# PX4FLOW2_0_Connectors_X0.net
KiCad netlist of a schematic drawn in Altium Designer
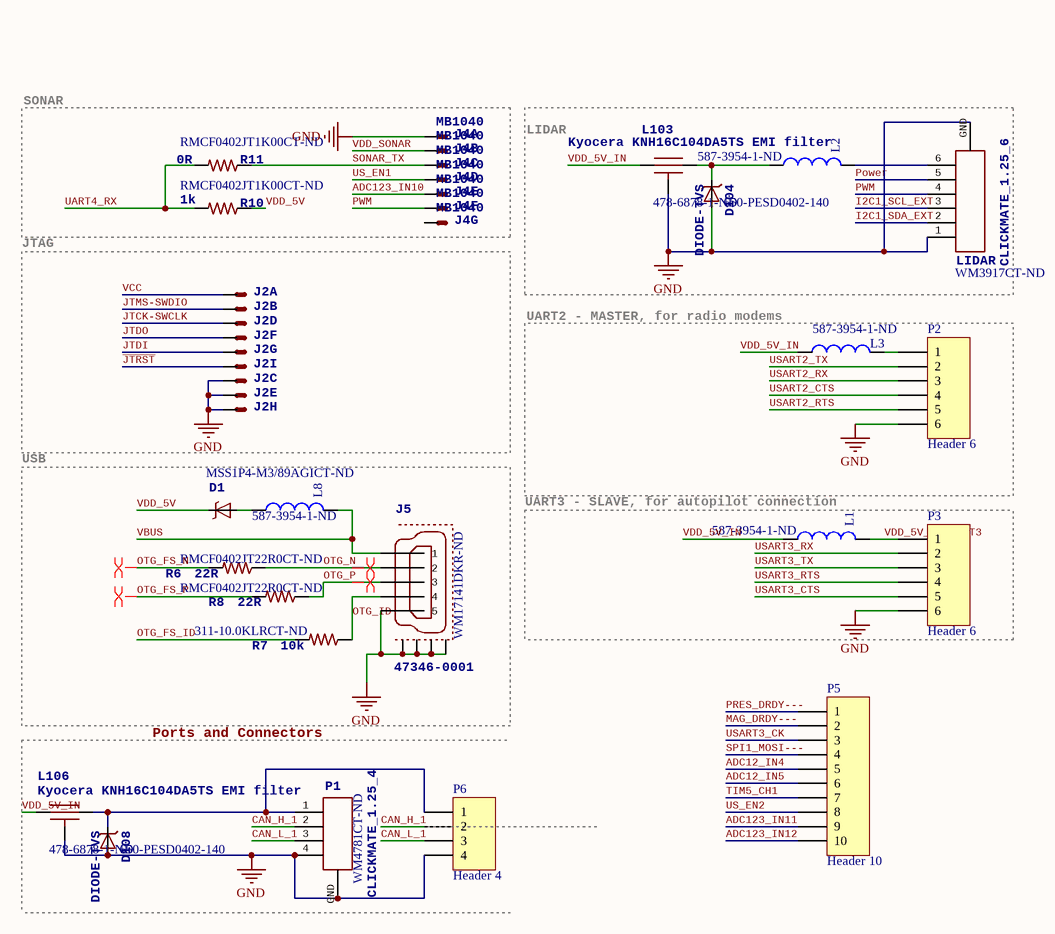
[diagram p0: PX4FLOW2.0_Connectors_X0.SchDoc]

(export (version "E")
  (design (tool "Eeschema 10.0.6"))
  (components
    (comp (ref "D1")
      (value "MSS1P4-M3")
      (footprint "MICROSMP")
      (description "Schottky barrier diode in DO214AC, e.g. Fairchild SS14.")
      (fields (field (name "SUPPLIER PART NUMBER 1") "MSS1P4-M3/89AGICT-ND"))
      (libsource (lib "pixhawk2") (part "DIODE-SCHOTTKY_MSMP"))
    )
    (comp (ref "D104")
      (value "DIODE-TVS")
      (footprint "0402-TVS")
      (description "Diode, TVS, 14VWM, 40VC, 0402, SMD")
      (fields
        (field (name "SUPPLIER PART NUMBER 1") "650-PESD0402-140")
        (field (name "3DR_PARTNO") "ECM0837")
      )
      (libsource (lib "PCA_0005_FULL_CB_REV_A") (part "DIODE-TVS"))
    )
    (comp (ref "D108")
      (value "DIODE-TVS")
      (footprint "0402-TVS")
      (description "Diode, TVS, 14VWM, 40VC, 0402, SMD")
      (fields
        (field (name "SUPPLIER PART NUMBER 1") "650-PESD0402-140")
        (field (name "3DR_PARTNO") "ECM0837")
      )
      (libsource (lib "PCA_0005_FULL_CB_REV_A") (part "DIODE-TVS"))
    )
    (comp (ref "J2")
      (value "~")
      (footprint "FTSH-105-01-XXX-DV-K")
      (libsource (lib "pixhawk2") (part "ARM_MINI_JTAG-SMT"))
    )
    (comp (ref "J4") (value "MB1040") (footprint "MAXSONAR") (libsource (lib "pixhawk2") (part "MAXSONAR")))
    (comp (ref "J5")
      (value "47346-0001")
      (footprint "MOLEX-47346-0001")
      (description "MICRO USB B, BOTTOM MOUNT")
      (fields
        (field (name "SUPPLIER PART NUMBER 1") "WM17141DKR-ND")
        (field (name "3DR_PARTNO") "ECM0486")
        (field (name "PARTNO") "0473460001")
      )
      (libsource (lib "pixhawk2") (part "MOLEX-47346-0001"))
    )
    (comp (ref "L1")
      (value "Inductor")
      (footprint "L0402")
      (description "FERRITE BEAD 120 OHM 0402")
      (fields (field (name "SUPPLIER PART NUMBER 1") "587-3954-1-ND"))
      (libsource (lib "3DR") (part "Inductor"))
    )
    (comp (ref "L2")
      (value "Inductor")
      (footprint "L0402")
      (description "FERRITE BEAD 120 OHM 0402")
      (fields (field (name "SUPPLIER PART NUMBER 1") "587-3954-1-ND"))
      (libsource (lib "3DR") (part "Inductor"))
    )
    (comp (ref "L3")
      (value "Inductor")
      (footprint "L0402")
      (description "FERRITE BEAD 120 OHM 0402")
      (fields (field (name "SUPPLIER PART NUMBER 1") "587-3954-1-ND"))
      (libsource (lib "3DR") (part "Inductor"))
    )
    (comp (ref "L8")
      (value "FERRITE BEAD 120 OHM 0402")
      (footprint "L0402")
      (fields (field (name "SUPPLIER PART NUMBER 1") "587-3954-1-ND"))
      (libsource (lib "3DR") (part "Inductor"))
    )
    (comp (ref "L103")
      (value "Kyocera KNH16C104DA5TS EMI filter")
      (footprint "KYOCERA-KNH16-DA")
      (description "Capacitor, Filter, 0.1uF, 25V, 2A, 0603, SMD")
      (fields (field (name "SUPPLIER PART NUMBER 1") "478-6878-1-ND") (field (name "3DR_PARTNO") "ECM0719"))
      (libsource (lib "PCA_0005_FULL_CB_REV_A") (part "KNH16C104DA5TS"))
    )
    (comp (ref "L106")
      (value "Kyocera KNH16C104DA5TS EMI filter")
      (footprint "KYOCERA-KNH16-DA")
      (description "Capacitor, Filter, 0.1uF, 25V, 2A, 0603, SMD")
      (fields (field (name "SUPPLIER PART NUMBER 1") "478-6878-1-ND") (field (name "3DR_PARTNO") "ECM0719"))
      (libsource (lib "PCA_0005_FULL_CB_REV_A") (part "KNH16C104DA5TS"))
    )
    (comp (ref "LIDAR")
      (value "CLICKMATE_1.25_6")
      (footprint "CLICKMATE_H6")
      (description "1.25 W/B SGL R/A REC ASSY 6CKT")
      (fields (field (name "3DR_PARTNO") "ECM0532") (field (name "SUPPLIER PART NUMBER 1") "WM3917CT-ND"))
      (libsource (lib "PCA_0005_FULL_CB_REV_A") (part "CLICKMATE_1.25_6"))
    )
    (comp (ref "P1")
      (value "CLICKMATE_1.25_4")
      (footprint "CLICKMATE_V4")
      (description "Connector, Rcpt, 4Pos, 1.25MM, W/B, VERT, SMD, Tin")
      (fields (field (name "SUPPLIER PART NUMBER 1") "WM4781CT-ND") (field (name "3DR_PARTNO") "PRT0441"))
      (libsource (lib "PCA_0005_FULL_CB_REV_A") (part "CLICKMATE_1.25_4"))
    )
    (comp (ref "P2")
      (value "Header 6")
      (footprint "HDR1X6")
      (description "Header, 6-Pin")
      (fields (field (name "PUBLISHER") "Altium Limited"))
      (libsource (lib "Miscellaneous Connectors") (part "Header 6"))
    )
    (comp (ref "P3")
      (value "Header 6")
      (footprint "HDR1X6")
      (description "Header, 6-Pin")
      (fields (field (name "PUBLISHER") "Altium Limited"))
      (libsource (lib "Miscellaneous Connectors") (part "Header 6"))
    )
    (comp (ref "P5")
      (value "Header 10")
      (footprint "HDR1X10")
      (description "Header, 10-Pin")
      (fields (field (name "PUBLISHER") "Altium Limited"))
      (libsource (lib "Miscellaneous Connectors") (part "Header 10"))
    )
    (comp (ref "P6")
      (value "Header 4")
      (footprint "HDR1X4")
      (description "Header, 4-Pin")
      (fields (field (name "PUBLISHER") "Altium Limited"))
      (libsource (lib "Miscellaneous Connectors") (part "Header 4"))
    )
    (comp (ref "R6")
      (value "22R")
      (footprint "R0402")
      (fields
        (field (name "PARTNO") "RMCF0402JT22R0")
        (field (name "SUPPLIER PART NUMBER 1") "RMCF0402JT22R0CT-ND")
      )
      (libsource (lib "pixhawk2") (part "RESISTOR0402-RES"))
    )
    (comp (ref "R7")
      (value "10k")
      (footprint "R0402")
      (description "RES 10K OHM 1/16W 1% 0402 SMD")
      (fields
        (field (name "PARTNO") "MFR-25FBF-10K0")
        (field (name "SUPPLIER PART NUMBER 1") "311-10.0KLRCT-ND")
      )
      (libsource (lib "pixhawk2") (part "RESISTOR0402-RES"))
    )
    (comp (ref "R8")
      (value "22R")
      (footprint "R0402")
      (fields
        (field (name "PARTNO") "RMCF0402JT22R0")
        (field (name "SUPPLIER PART NUMBER 1") "RMCF0402JT22R0CT-ND")
      )
      (libsource (lib "pixhawk2") (part "RESISTOR0402-RES"))
    )
    (comp (ref "R10")
      (value "1k")
      (footprint "R0402")
      (fields
        (field (name "PARTNO") "RMCF0402JT1K00")
        (field (name "SUPPLIER PART NUMBER 1") "RMCF0402JT1K00CT-ND")
      )
      (libsource (lib "pixhawk2") (part "RESISTOR0402-RES"))
    )
    (comp (ref "R11")
      (value "0R")
      (footprint "R0402")
      (fields
        (field (name "PARTNO") "RMCF0402JT1K00")
        (field (name "SUPPLIER PART NUMBER 1") "RMCF0402JT1K00CT-ND")
      )
      (libsource (lib "pixhawk2") (part "RESISTOR0402-RES"))
    )
  )
  (nets
    (net (code "1") (name "/ADC12_IN4") (class "Default")
      (node (ref "P5") (pin "5") (pinfunction "5_5") (pintype "passive"))
    )
    (net (code "2") (name "/ADC12_IN5") (class "Default")
      (node (ref "P5") (pin "6") (pinfunction "6_6") (pintype "passive"))
    )
    (net (code "3") (name "/ADC123_IN10") (class "Default")
      (node (ref "J4") (pin "AN") (pinfunction "S_AN") (pintype "passive"))
    )
    (net (code "4") (name "/ADC123_IN11") (class "Default")
      (node (ref "P5") (pin "9") (pinfunction "9_9") (pintype "passive"))
    )
    (net (code "5") (name "/ADC123_IN12") (class "Default")
      (node (ref "P5") (pin "10") (pinfunction "10_10") (pintype "passive"))
    )
    (net (code "6") (name "/CAN_H_1") (class "Default")
      (node (ref "P1") (pin "2") (pinfunction "2_2") (pintype "passive"))
      (node (ref "P6") (pin "2") (pinfunction "2_2") (pintype "passive"))
    )
    (net (code "7") (name "/CAN_L_1") (class "Default")
      (node (ref "P1") (pin "3") (pinfunction "3_3") (pintype "passive"))
      (node (ref "P6") (pin "3") (pinfunction "3_3") (pintype "passive"))
    )
    (net (code "8") (name "/I2C1_SCL_EXT") (class "Default")
      (node (ref "LIDAR") (pin "3") (pinfunction "3_3") (pintype "passive"))
    )
    (net (code "9") (name "/I2C1_SDA_EXT") (class "Default")
      (node (ref "LIDAR") (pin "2") (pinfunction "2_2") (pintype "passive"))
    )
    (net (code "10") (name "/JTCK-SWCLK") (class "Default")
      (node (ref "J2") (pin "4") (pinfunction "S_4") (pintype "passive"))
    )
    (net (code "11") (name "/JTDI") (class "Default")
      (node (ref "J2") (pin "8") (pinfunction "S_8") (pintype "passive"))
    )
    (net (code "12") (name "/JTDO") (class "Default")
      (node (ref "J2") (pin "6") (pinfunction "S_6") (pintype "passive"))
    )
    (net (code "13") (name "/JTMS-SWDIO") (class "Default")
      (node (ref "J2") (pin "2") (pinfunction "S_2") (pintype "passive"))
    )
    (net (code "14") (name "/MAG_DRDY---") (class "Default")
      (node (ref "P5") (pin "2") (pinfunction "2_2") (pintype "passive"))
    )
    (net (code "15") (name "/OTG_FS_ID") (class "Default")
      (node (ref "R7") (pin "2") (pinfunction "2_2") (pintype "passive"))
    )
    (net (code "16") (name "/OTG_FS_N") (class "Default")
      (node (ref "R6") (pin "2") (pinfunction "2_2") (pintype "passive"))
    )
    (net (code "17") (name "/OTG_FS_P") (class "Default")
      (node (ref "R8") (pin "2") (pinfunction "2_2") (pintype "passive"))
    )
    (net (code "18") (name "/OTG_ID") (class "Default")
      (node (ref "J5") (pin "ID") (pinfunction "4_ID") (pintype "passive"))
      (node (ref "R7") (pin "1") (pinfunction "1_1") (pintype "passive"))
    )
    (net (code "19") (name "/OTG_N") (class "Default")
      (node (ref "J5") (pin "D-") (pinfunction "2_D-") (pintype "passive"))
      (node (ref "R6") (pin "1") (pinfunction "1_1") (pintype "passive"))
    )
    (net (code "20") (name "/OTG_P") (class "Default")
      (node (ref "J5") (pin "D+") (pinfunction "3_D+") (pintype "passive"))
      (node (ref "R8") (pin "1") (pinfunction "1_1") (pintype "passive"))
    )
    (net (code "21") (name "/PRES_DRDY---") (class "Default")
      (node (ref "P5") (pin "1") (pinfunction "1_1") (pintype "passive"))
    )
    (net (code "22") (name "/PWM") (class "Default")
      (node (ref "J4") (pin "PW") (pinfunction "S_PW") (pintype "passive"))
      (node (ref "LIDAR") (pin "4") (pinfunction "4_4") (pintype "passive"))
    )
    (net (code "23") (name "/Power") (class "Default")
      (node (ref "LIDAR") (pin "5") (pinfunction "5_5") (pintype "passive"))
    )
    (net (code "24") (name "/SONAR_TX") (class "Default")
      (node (ref "J4") (pin "TX") (pinfunction "S_TX") (pintype "passive"))
      (node (ref "R11") (pin "1") (pinfunction "1_1") (pintype "passive"))
    )
    (net (code "25") (name "/SPI1_MOSI---") (class "Default")
      (node (ref "P5") (pin "4") (pinfunction "4_4") (pintype "passive"))
    )
    (net (code "26") (name "/TIM5_CH1") (class "Default")
      (node (ref "P5") (pin "7") (pinfunction "7_7") (pintype "passive"))
    )
    (net (code "27") (name "/UART4_RX") (class "Default")
      (node (ref "R10") (pin "2") (pinfunction "2_2") (pintype "passive"))
      (node (ref "R11") (pin "2") (pinfunction "2_2") (pintype "passive"))
    )
    (net (code "28") (name "/USART2_CTS") (class "Default")
      (node (ref "P2") (pin "4") (pinfunction "4_4") (pintype "passive"))
    )
    (net (code "29") (name "/USART2_RTS") (class "Default")
      (node (ref "P2") (pin "5") (pinfunction "5_5") (pintype "passive"))
    )
    (net (code "30") (name "/USART2_RX") (class "Default")
      (node (ref "P2") (pin "3") (pinfunction "3_3") (pintype "passive"))
    )
    (net (code "31") (name "/USART2_TX") (class "Default")
      (node (ref "P2") (pin "2") (pinfunction "2_2") (pintype "passive"))
    )
    (net (code "32") (name "/USART3_CK") (class "Default")
      (node (ref "P5") (pin "3") (pinfunction "3_3") (pintype "passive"))
    )
    (net (code "33") (name "/USART3_CTS") (class "Default")
      (node (ref "P3") (pin "5") (pinfunction "5_5") (pintype "passive"))
    )
    (net (code "34") (name "/USART3_RTS") (class "Default")
      (node (ref "P3") (pin "4") (pinfunction "4_4") (pintype "passive"))
    )
    (net (code "35") (name "/USART3_RX") (class "Default")
      (node (ref "P3") (pin "2") (pinfunction "2_2") (pintype "passive"))
    )
    (net (code "36") (name "/USART3_TX") (class "Default")
      (node (ref "P3") (pin "3") (pinfunction "3_3") (pintype "passive"))
    )
    (net (code "37") (name "/US_EN1") (class "Default")
      (node (ref "J4") (pin "RX") (pinfunction "S_RX") (pintype "passive"))
    )
    (net (code "38") (name "/US_EN2") (class "Default")
      (node (ref "P5") (pin "8") (pinfunction "8_8") (pintype "passive"))
    )
    (net (code "39") (name "/VBUS") (class "Default")
      (node (ref "J5") (pin "VBUS") (pinfunction "1_VBUS") (pintype "open_emitter"))
      (node (ref "L8") (pin "2") (pinfunction "2_2") (pintype "passive"))
    )
    (net (code "40") (name "/VCC") (class "Default")
      (node (ref "J2") (pin "1") (pinfunction "S_1") (pintype "passive"))
    )
    (net (code "41") (name "/VDD_5V") (class "Default")
      (node (ref "D1") (pin "CATHODE") (pinfunction "C_CATHODE") (pintype "passive"))
      (node (ref "R10") (pin "1") (pinfunction "1_1") (pintype "passive"))
    )
    (net (code "42") (name "/VDD_5V_IN") (class "Default")
      (node (ref "L1") (pin "1") (pinfunction "1_1") (pintype "passive"))
      (node (ref "L103") (pin "P$1") (pinfunction "P$1_P$1") (pintype "passive"))
      (node (ref "L106") (pin "P$1") (pinfunction "P$1_P$1") (pintype "passive"))
      (node (ref "L3") (pin "1") (pinfunction "1_1") (pintype "passive"))
    )
    (net (code "43") (name "/VDD_5V_IN_UART3") (class "Default")
      (node (ref "L1") (pin "2") (pinfunction "2_2") (pintype "passive"))
      (node (ref "P3") (pin "1") (pinfunction "1_1") (pintype "passive"))
    )
    (net (code "44") (name "/VDD_SONAR") (class "Default")
      (node (ref "J4") (pin "VDD") (pinfunction "S_VDD") (pintype "passive"))
    )
    (net (code "45") (name "/~{JTRST}") (class "Default")
      (node (ref "J2") (pin "10") (pinfunction "S_10") (pintype "passive"))
    )
    (net (code "46") (name "GND") (class "Default")
      (node (ref "D104") (pin "A") (pinfunction "A_A") (pintype "passive"))
      (node (ref "D108") (pin "A") (pinfunction "A_A") (pintype "passive"))
      (node (ref "J2") (pin "3") (pinfunction "S_3") (pintype "passive"))
      (node (ref "J2") (pin "5") (pinfunction "S_5") (pintype "passive"))
      (node (ref "J2") (pin "9") (pinfunction "S_9") (pintype "passive"))
      (node (ref "J4") (pin "GND") (pinfunction "S_GND") (pintype "passive"))
      (node (ref "J5") (pin "GND") (pinfunction "5_GND") (pintype "power_in"))
      (node (ref "J5") (pin "GND1") (pinfunction "GND1_GND1") (pintype "passive"))
      (node (ref "J5") (pin "GND2") (pinfunction "GND2_GND2") (pintype "passive"))
      (node (ref "J5") (pin "GND3") (pinfunction "GND3_GND3") (pintype "passive"))
      (node (ref "J5") (pin "GND4") (pinfunction "GND4_GND4") (pintype "passive"))
      (node (ref "L103") (pin "GND") (pinfunction "GND_GND") (pintype "passive"))
      (node (ref "L106") (pin "GND") (pinfunction "GND_GND") (pintype "passive"))
      (node (ref "LIDAR") (pin "1") (pinfunction "1_1") (pintype "passive"))
      (node (ref "LIDAR") (pin "GND") (pinfunction "GND_GND") (pintype "passive"))
      (node (ref "P1") (pin "4") (pinfunction "4_4") (pintype "passive"))
      (node (ref "P1") (pin "GND") (pinfunction "GND_GND") (pintype "passive"))
      (node (ref "P2") (pin "6") (pinfunction "6_6") (pintype "passive"))
      (node (ref "P3") (pin "6") (pinfunction "6_6") (pintype "passive"))
      (node (ref "P6") (pin "4") (pinfunction "4_4") (pintype "passive"))
    )
    (net (code "47") (name "Net-(D1-A)") (class "Default")
      (node (ref "D1") (pin "ANODE") (pinfunction "A_ANODE") (pintype "passive"))
      (node (ref "L8") (pin "1") (pinfunction "1_1") (pintype "passive"))
    )
    (net (code "48") (name "Net-(D104-PadC)") (class "Default")
      (node (ref "D104") (pin "C") (pinfunction "C_C") (pintype "passive"))
      (node (ref "L103") (pin "P$2") (pinfunction "P$2_P$2") (pintype "passive"))
      (node (ref "L2") (pin "1") (pinfunction "1_1") (pintype "passive"))
    )
    (net (code "49") (name "Net-(D108-PadC)") (class "Default")
      (node (ref "D108") (pin "C") (pinfunction "C_C") (pintype "passive"))
      (node (ref "L106") (pin "P$2") (pinfunction "P$2_P$2") (pintype "passive"))
      (node (ref "P1") (pin "1") (pinfunction "1_1") (pintype "passive"))
      (node (ref "P6") (pin "1") (pinfunction "1_1") (pintype "passive"))
    )
    (net (code "50") (name "Net-(L2-Pad2)") (class "Default")
      (node (ref "L2") (pin "2") (pinfunction "2_2") (pintype "passive"))
      (node (ref "LIDAR") (pin "6") (pinfunction "6_6") (pintype "passive"))
    )
    (net (code "51") (name "Net-(L3-Pad2)") (class "Default")
      (node (ref "L3") (pin "2") (pinfunction "2_2") (pintype "passive"))
      (node (ref "P2") (pin "1") (pinfunction "1_1") (pintype "passive"))
    )
    (net (code "52") (name "unconnected-(J4G-S-PadBW)") (class "Default")
      (node (ref "J4") (pin "BW") (pinfunction "S_BW") (pintype "passive"))
    )
  )
)
